# Bee_Snuggler_-_Main.net
KiCad netlist of a schematic drawn in EAGLE
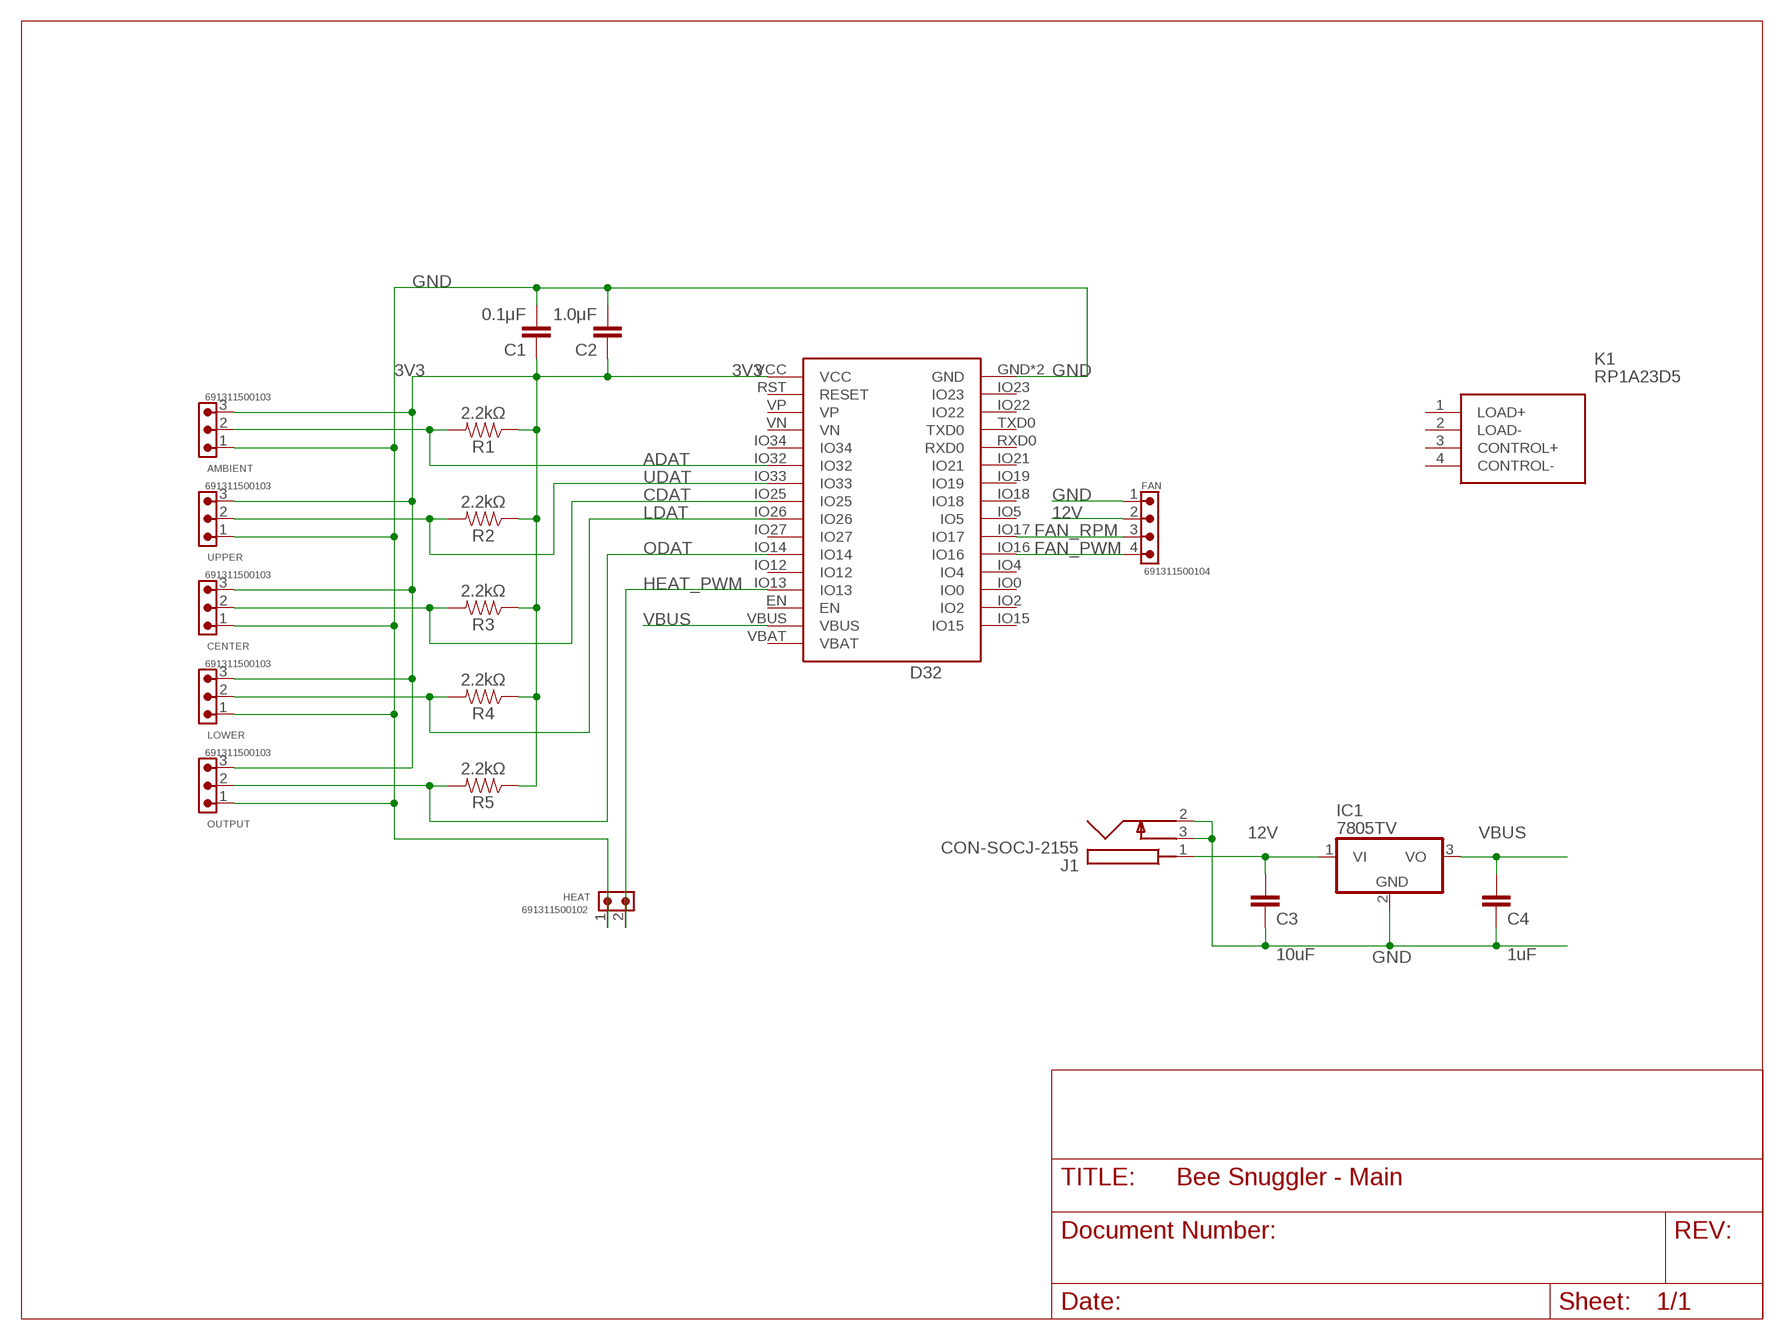
[diagram p0: schematic, sheet 1]

(export (version "E")
  (design (tool "Eeschema 10.0.6"))
  (components
    (comp (ref "AMBIENT")
      (value "691311500103")
      (footprint "eagle-import:691311500103")
      (libsource (lib "eagle-import") (part "691311500103"))
    )
    (comp (ref "C1")
      (value "0.1μF")
      (footprint "eagle-import:CAP_PTH-2.54")
      (libsource (lib "eagle-import") (part "CAP_CERAMIC_2.54"))
    )
    (comp (ref "C2")
      (value "1.0μF")
      (footprint "eagle-import:CAP_PTH-2.54")
      (libsource (lib "eagle-import") (part "CAP_CERAMIC_2.54"))
    )
    (comp (ref "C3")
      (value "10uF")
      (footprint "eagle-import:CAP_PTH-2.54")
      (libsource (lib "eagle-import") (part "CAP_CERAMIC_2.54"))
    )
    (comp (ref "C4")
      (value "1uF")
      (footprint "eagle-import:CAP_PTH-2.54")
      (libsource (lib "eagle-import") (part "CAP_CERAMIC_2.54"))
    )
    (comp (ref "CENTER")
      (value "691311500103")
      (footprint "eagle-import:691311500103")
      (libsource (lib "eagle-import") (part "691311500103"))
    )
    (comp (ref "D32")
      (value "Lolin D32")
      (footprint "eagle-import:D32_PRO")
      (libsource (lib "eagle-import") (part "WEMOS-D32D32_PRO"))
    )
    (comp (ref "FAN")
      (value "691311500104")
      (footprint "eagle-import:691311500104")
      (libsource (lib "eagle-import") (part "691311500104"))
    )
    (comp (ref "HEAT")
      (value "691311500102")
      (footprint "eagle-import:691311500102")
      (libsource (lib "eagle-import") (part "691311500102"))
    )
    (comp (ref "IC1")
      (value "7805TV")
      (footprint "eagle-import:TO220V")
      (libsource (lib "eagle-import") (part "78TV05"))
    )
    (comp (ref "J1")
      (value "CON-SOCJ-2155")
      (footprint "eagle-import:CONSOCJ2155")
      (fields (field (name "MOUSER_PART_NUMBER") "992-CON-SOCJ-2155"))
      (libsource (lib "eagle-import") (part "CON-SOCJ-2155"))
    )
    (comp (ref "K1")
      (value "RP1A23D5")
      (footprint "eagle-import:RP1A23D5")
      (fields (field (name "MOUSER_PART_NUMBER") "225-RP1A23D5"))
      (libsource (lib "eagle-import") (part "RP1A23D5"))
    )
    (comp (ref "LOWER")
      (value "691311500103")
      (footprint "eagle-import:691311500103")
      (libsource (lib "eagle-import") (part "691311500103"))
    )
    (comp (ref "OUTPUT")
      (value "691311500103")
      (footprint "eagle-import:691311500103")
      (libsource (lib "eagle-import") (part "691311500103"))
    )
    (comp (ref "R1")
      (value "2.2kΩ")
      (footprint "eagle-import:AXIAL-0.3")
      (libsource (lib "eagle-import") (part "RESISTORAXIAL-0.3"))
    )
    (comp (ref "R2")
      (value "2.2kΩ")
      (footprint "eagle-import:AXIAL-0.3")
      (libsource (lib "eagle-import") (part "RESISTORAXIAL-0.3"))
    )
    (comp (ref "R3")
      (value "2.2kΩ")
      (footprint "eagle-import:AXIAL-0.3")
      (libsource (lib "eagle-import") (part "RESISTORAXIAL-0.3"))
    )
    (comp (ref "R4")
      (value "2.2kΩ")
      (footprint "eagle-import:AXIAL-0.3")
      (libsource (lib "eagle-import") (part "RESISTORAXIAL-0.3"))
    )
    (comp (ref "R5")
      (value "2.2kΩ")
      (footprint "eagle-import:AXIAL-0.3")
      (libsource (lib "eagle-import") (part "RESISTORAXIAL-0.3"))
    )
    (comp (ref "UPPER")
      (value "691311500103")
      (footprint "eagle-import:691311500103")
      (libsource (lib "eagle-import") (part "691311500103"))
    )
  )
  (nets
    (net (code "1") (name "/3V3") (class "Default")
      (node (ref "AMBIENT") (pin "3") (pinfunction "3_3") (pintype "passive"))
      (node (ref "C1") (pin "1") (pinfunction "1_1") (pintype "passive"))
      (node (ref "C2") (pin "1") (pinfunction "1_1") (pintype "passive"))
      (node (ref "CENTER") (pin "3") (pinfunction "3_3") (pintype "passive"))
      (node (ref "D32") (pin "VCC") (pinfunction "VCC_VCC") (pintype "power_in"))
      (node (ref "LOWER") (pin "3") (pinfunction "3_3") (pintype "passive"))
      (node (ref "OUTPUT") (pin "3") (pinfunction "3_3") (pintype "passive"))
      (node (ref "R1") (pin "P$1") (pinfunction "1_P$1") (pintype "passive"))
      (node (ref "R2") (pin "P$1") (pinfunction "1_P$1") (pintype "passive"))
      (node (ref "R3") (pin "P$1") (pinfunction "1_P$1") (pintype "passive"))
      (node (ref "R4") (pin "P$1") (pinfunction "1_P$1") (pintype "passive"))
      (node (ref "R5") (pin "P$1") (pinfunction "1_P$1") (pintype "passive"))
      (node (ref "UPPER") (pin "3") (pinfunction "3_3") (pintype "passive"))
    )
    (net (code "2") (name "/12V") (class "Default")
      (node (ref "C3") (pin "1") (pinfunction "1_1") (pintype "passive"))
      (node (ref "FAN") (pin "2") (pinfunction "2_2") (pintype "passive"))
      (node (ref "IC1") (pin "1") (pinfunction "VI_1") (pintype "input"))
      (node (ref "J1") (pin "1") (pinfunction "1_1") (pintype "bidirectional"))
    )
    (net (code "3") (name "/ADAT") (class "Default")
      (node (ref "AMBIENT") (pin "2") (pinfunction "2_2") (pintype "passive"))
      (node (ref "D32") (pin "IO32") (pinfunction "IO32_IO32") (pintype "bidirectional"))
      (node (ref "R1") (pin "P$2") (pinfunction "2_P$2") (pintype "passive"))
    )
    (net (code "4") (name "/CDAT") (class "Default")
      (node (ref "CENTER") (pin "2") (pinfunction "2_2") (pintype "passive"))
      (node (ref "D32") (pin "IO25") (pinfunction "IO25_IO25") (pintype "bidirectional"))
      (node (ref "R3") (pin "P$2") (pinfunction "2_P$2") (pintype "passive"))
    )
    (net (code "5") (name "/FAN_PWM") (class "Default")
      (node (ref "D32") (pin "IO16") (pinfunction "IO16_IO16") (pintype "bidirectional"))
      (node (ref "FAN") (pin "4") (pinfunction "4_4") (pintype "passive"))
    )
    (net (code "6") (name "/FAN_RPM") (class "Default")
      (node (ref "D32") (pin "IO17") (pinfunction "IO17_IO17") (pintype "bidirectional"))
      (node (ref "FAN") (pin "3") (pinfunction "3_3") (pintype "passive"))
    )
    (net (code "7") (name "/GND") (class "Default")
      (node (ref "AMBIENT") (pin "1") (pinfunction "1_1") (pintype "passive"))
      (node (ref "C1") (pin "2") (pinfunction "2_2") (pintype "passive"))
      (node (ref "C2") (pin "2") (pinfunction "2_2") (pintype "passive"))
      (node (ref "C3") (pin "2") (pinfunction "2_2") (pintype "passive"))
      (node (ref "C4") (pin "2") (pinfunction "2_2") (pintype "passive"))
      (node (ref "CENTER") (pin "1") (pinfunction "1_1") (pintype "passive"))
      (node (ref "D32") (pin "GND") (pinfunction "GND_GND") (pintype "power_in"))
      (node (ref "D32") (pin "GND2") (pinfunction "GND_GND2") (pintype "power_in"))
      (node (ref "FAN") (pin "1") (pinfunction "1_1") (pintype "passive"))
      (node (ref "HEAT") (pin "1") (pinfunction "1_1") (pintype "passive"))
      (node (ref "IC1") (pin "2") (pinfunction "GND_2") (pintype "passive"))
      (node (ref "J1") (pin "2") (pinfunction "2_2") (pintype "bidirectional"))
      (node (ref "J1") (pin "3") (pinfunction "3_3") (pintype "bidirectional"))
      (node (ref "LOWER") (pin "1") (pinfunction "1_1") (pintype "passive"))
      (node (ref "OUTPUT") (pin "1") (pinfunction "1_1") (pintype "passive"))
      (node (ref "UPPER") (pin "1") (pinfunction "1_1") (pintype "passive"))
    )
    (net (code "8") (name "/HEAT_PWM") (class "Default")
      (node (ref "D32") (pin "IO13") (pinfunction "IO13_IO13") (pintype "bidirectional"))
      (node (ref "HEAT") (pin "2") (pinfunction "2_2") (pintype "passive"))
    )
    (net (code "9") (name "/LDAT") (class "Default")
      (node (ref "D32") (pin "IO26") (pinfunction "IO26_IO26") (pintype "bidirectional"))
      (node (ref "LOWER") (pin "2") (pinfunction "2_2") (pintype "passive"))
      (node (ref "R4") (pin "P$2") (pinfunction "2_P$2") (pintype "passive"))
    )
    (net (code "10") (name "/ODAT") (class "Default")
      (node (ref "D32") (pin "IO14") (pinfunction "IO14_IO14") (pintype "bidirectional"))
      (node (ref "OUTPUT") (pin "2") (pinfunction "2_2") (pintype "passive"))
      (node (ref "R5") (pin "P$2") (pinfunction "2_P$2") (pintype "passive"))
    )
    (net (code "11") (name "/UDAT") (class "Default")
      (node (ref "D32") (pin "IO33") (pinfunction "IO33_IO33") (pintype "bidirectional"))
      (node (ref "R2") (pin "P$2") (pinfunction "2_P$2") (pintype "passive"))
      (node (ref "UPPER") (pin "2") (pinfunction "2_2") (pintype "passive"))
    )
    (net (code "12") (name "/VBUS") (class "Default")
      (node (ref "C4") (pin "1") (pinfunction "1_1") (pintype "passive"))
      (node (ref "D32") (pin "VBUS") (pinfunction "VBUS_VBUS") (pintype "bidirectional"))
      (node (ref "IC1") (pin "3") (pinfunction "VO_3") (pintype "passive"))
    )
    (net (code "13") (name "unconnected-(D32-PadEN)") (class "Default")
      (node (ref "D32") (pin "EN") (pinfunction "EN_EN") (pintype "bidirectional"))
    )
    (net (code "14") (name "unconnected-(D32-PadIO0)") (class "Default")
      (node (ref "D32") (pin "IO0") (pinfunction "IO0_IO0") (pintype "bidirectional"))
    )
    (net (code "15") (name "unconnected-(D32-PadIO2)") (class "Default")
      (node (ref "D32") (pin "IO2") (pinfunction "IO2_IO2") (pintype "bidirectional"))
    )
    (net (code "16") (name "unconnected-(D32-PadIO4)") (class "Default")
      (node (ref "D32") (pin "IO4") (pinfunction "IO4_IO4") (pintype "bidirectional"))
    )
    (net (code "17") (name "unconnected-(D32-PadIO5)") (class "Default")
      (node (ref "D32") (pin "IO5") (pinfunction "IO5_IO5") (pintype "bidirectional"))
    )
    (net (code "18") (name "unconnected-(D32-PadIO12)") (class "Default")
      (node (ref "D32") (pin "IO12") (pinfunction "IO12_IO12") (pintype "bidirectional"))
    )
    (net (code "19") (name "unconnected-(D32-PadIO15)") (class "Default")
      (node (ref "D32") (pin "IO15") (pinfunction "IO15_IO15") (pintype "bidirectional"))
    )
    (net (code "20") (name "unconnected-(D32-PadIO18)") (class "Default")
      (node (ref "D32") (pin "IO18") (pinfunction "IO18_IO18") (pintype "bidirectional"))
    )
    (net (code "21") (name "unconnected-(D32-PadIO19)") (class "Default")
      (node (ref "D32") (pin "IO19") (pinfunction "IO19_IO19") (pintype "bidirectional"))
    )
    (net (code "22") (name "unconnected-(D32-PadIO21)") (class "Default")
      (node (ref "D32") (pin "IO21") (pinfunction "IO21_IO21") (pintype "bidirectional"))
    )
    (net (code "23") (name "unconnected-(D32-PadIO22)") (class "Default")
      (node (ref "D32") (pin "IO22") (pinfunction "IO22_IO22") (pintype "bidirectional"))
    )
    (net (code "24") (name "unconnected-(D32-PadIO23)") (class "Default")
      (node (ref "D32") (pin "IO23") (pinfunction "IO23_IO23") (pintype "bidirectional"))
    )
    (net (code "25") (name "unconnected-(D32-PadIO27)") (class "Default")
      (node (ref "D32") (pin "IO27") (pinfunction "IO27_IO27") (pintype "bidirectional"))
    )
    (net (code "26") (name "unconnected-(D32-PadIO34)") (class "Default")
      (node (ref "D32") (pin "IO34") (pinfunction "IO34_IO34") (pintype "bidirectional"))
    )
    (net (code "27") (name "unconnected-(D32-PadRXD0)") (class "Default")
      (node (ref "D32") (pin "RXD0") (pinfunction "RXD0_RXD0") (pintype "input"))
    )
    (net (code "28") (name "unconnected-(D32-PadTXD0)") (class "Default")
      (node (ref "D32") (pin "TXD0") (pinfunction "TXD0_TXD0") (pintype "output"))
    )
    (net (code "29") (name "unconnected-(D32-PadVBAT)") (class "Default")
      (node (ref "D32") (pin "VBAT") (pinfunction "VBAT_VBAT") (pintype "bidirectional"))
    )
    (net (code "30") (name "unconnected-(D32-PadVN)") (class "Default")
      (node (ref "D32") (pin "VN") (pinfunction "VN_VN") (pintype "bidirectional"))
    )
    (net (code "31") (name "unconnected-(D32-PadVP)") (class "Default")
      (node (ref "D32") (pin "VP") (pinfunction "VP_VP") (pintype "bidirectional"))
    )
    (net (code "32") (name "unconnected-(D32-RESET-PadRST)") (class "Default")
      (node (ref "D32") (pin "RST") (pinfunction "RESET_RST") (pintype "bidirectional"))
    )
    (net (code "33") (name "unconnected-(K1-CONTROL+-Pad3)") (class "Default")
      (node (ref "K1") (pin "3") (pinfunction "CONTROL+_3") (pintype "bidirectional"))
    )
    (net (code "34") (name "unconnected-(K1-CONTROL--Pad4)") (class "Default")
      (node (ref "K1") (pin "4") (pinfunction "CONTROL-_4") (pintype "bidirectional"))
    )
    (net (code "35") (name "unconnected-(K1-LOAD+-Pad1)") (class "Default")
      (node (ref "K1") (pin "1") (pinfunction "LOAD+_1") (pintype "bidirectional"))
    )
    (net (code "36") (name "unconnected-(K1-LOAD--Pad2)") (class "Default")
      (node (ref "K1") (pin "2") (pinfunction "LOAD-_2") (pintype "bidirectional"))
    )
  )
)
